# JugendNetzteil.net
KiCad netlist of a schematic drawn in EAGLE
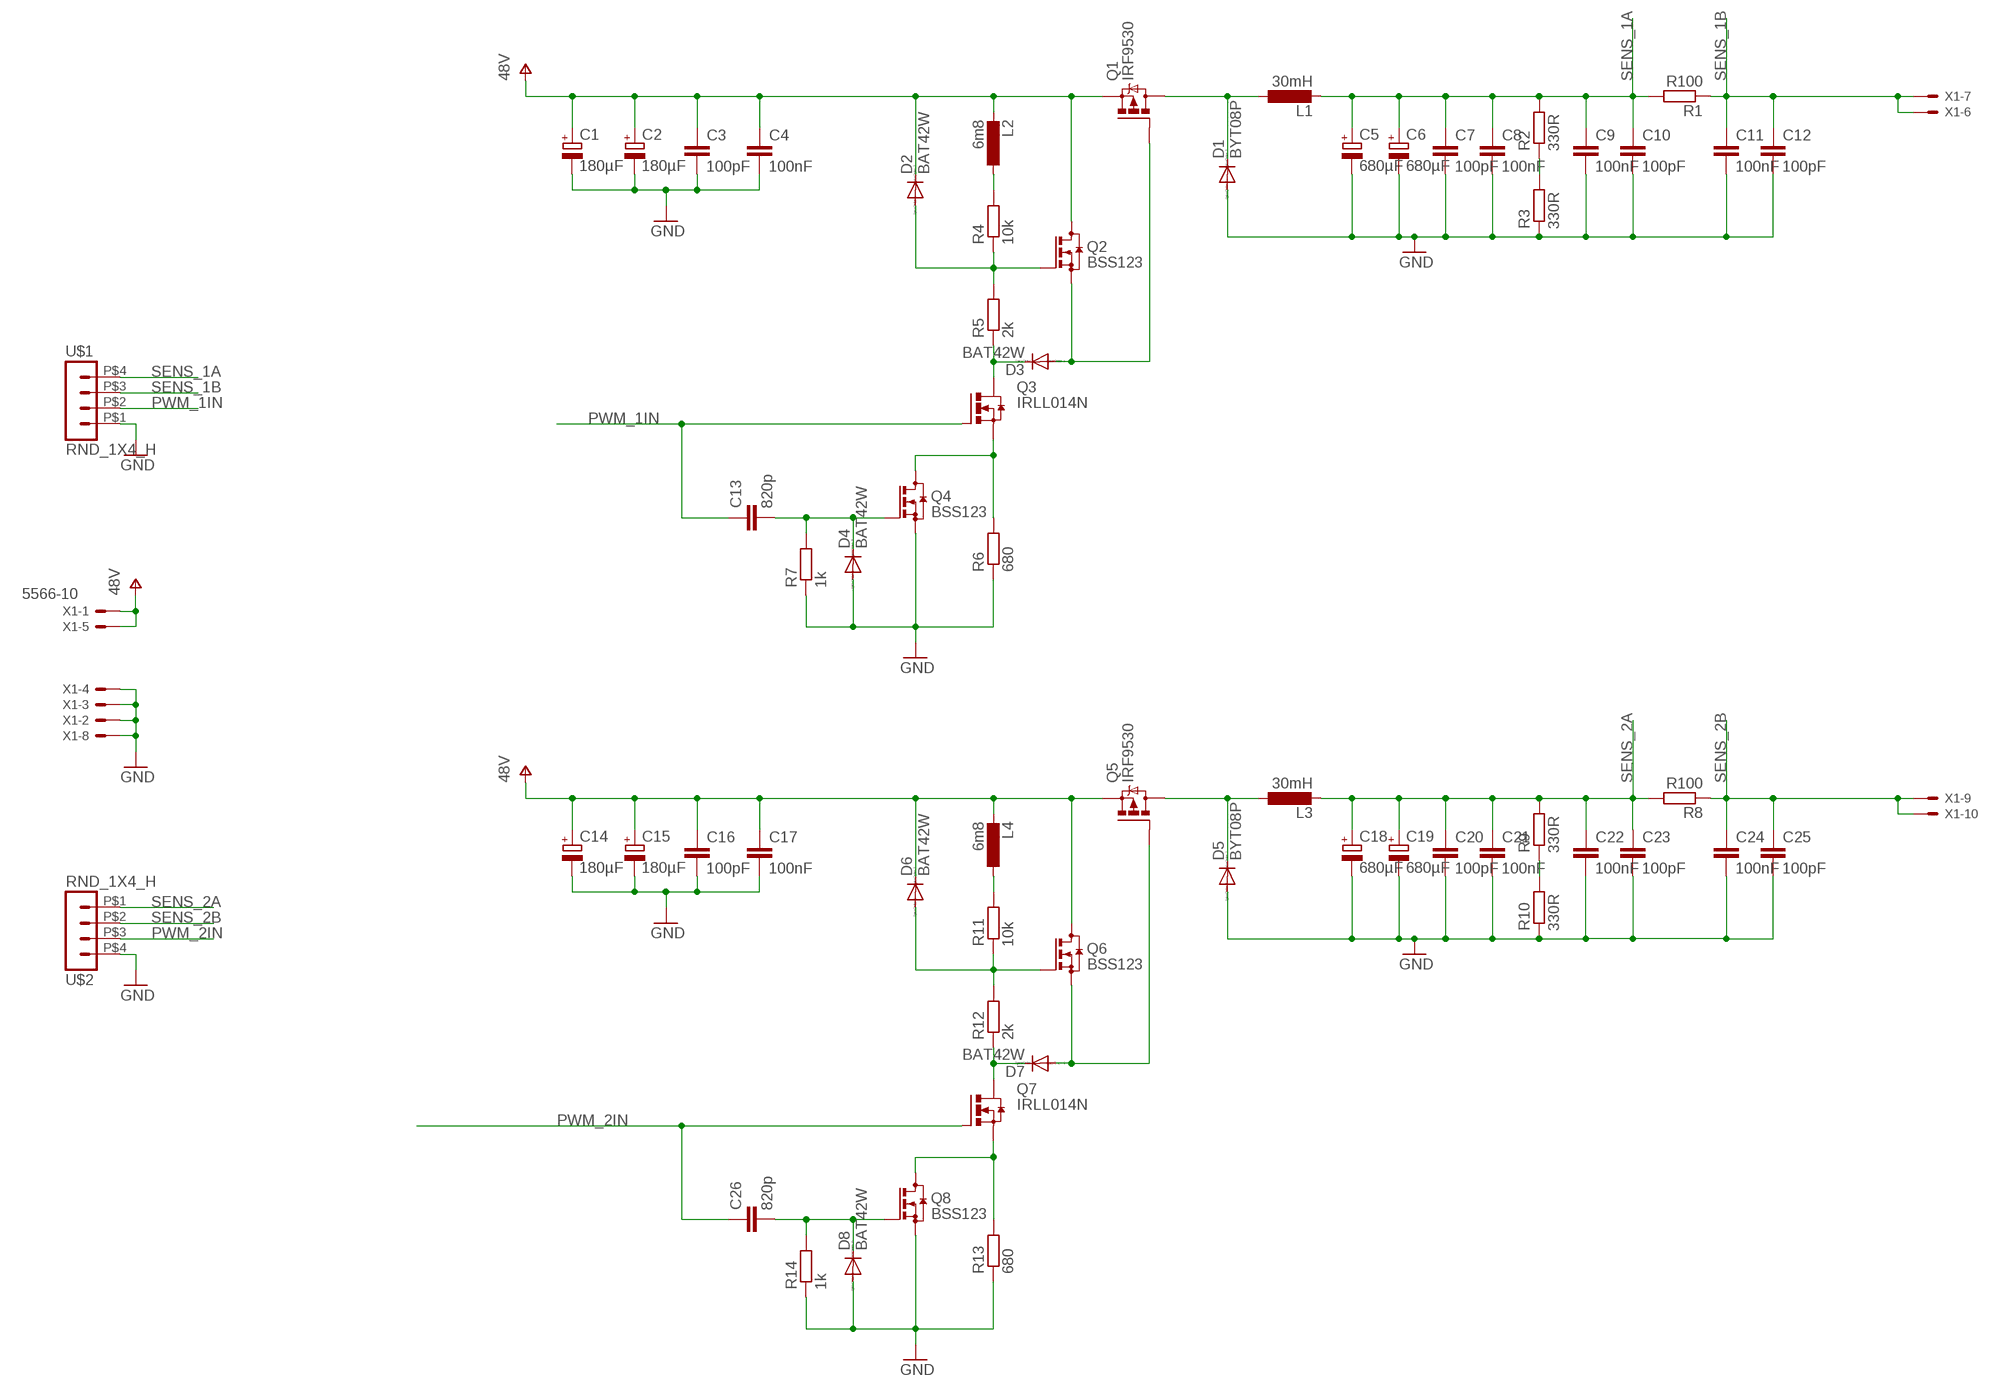
[diagram p0: schematic, sheet 1]

(export (version "E")
  (design (tool "Eeschema 10.0.6"))
  (components
    (comp (ref "C1")
      (value "180µF")
      (footprint "eagle-import:E3,5-8")
      (libsource (lib "eagle-import") (part "CPOL-EUE3.5-8"))
    )
    (comp (ref "C2")
      (value "180µF")
      (footprint "eagle-import:E3,5-8")
      (libsource (lib "eagle-import") (part "CPOL-EUE3.5-8"))
    )
    (comp (ref "C3")
      (value "100pF")
      (footprint "eagle-import:C0805")
      (libsource (lib "eagle-import") (part "C-EUC0805"))
    )
    (comp (ref "C4")
      (value "100nF")
      (footprint "eagle-import:C0805")
      (libsource (lib "eagle-import") (part "C-EUC0805"))
    )
    (comp (ref "C5")
      (value "680µF")
      (footprint "eagle-import:TT5D11")
      (libsource (lib "eagle-import") (part "CPOL-EUTT5D11"))
    )
    (comp (ref "C6")
      (value "680µF")
      (footprint "eagle-import:TT5D11")
      (libsource (lib "eagle-import") (part "CPOL-EUTT5D11"))
    )
    (comp (ref "C7")
      (value "100pF")
      (footprint "eagle-import:C0805")
      (libsource (lib "eagle-import") (part "C-EUC0805"))
    )
    (comp (ref "C8")
      (value "100nF")
      (footprint "eagle-import:C0805")
      (libsource (lib "eagle-import") (part "C-EUC0805"))
    )
    (comp (ref "C9")
      (value "100nF")
      (footprint "eagle-import:C0805")
      (libsource (lib "eagle-import") (part "C-EUC0805"))
    )
    (comp (ref "C10")
      (value "100pF")
      (footprint "eagle-import:C0805")
      (libsource (lib "eagle-import") (part "C-EUC0805"))
    )
    (comp (ref "C11")
      (value "100nF")
      (footprint "eagle-import:C0805")
      (libsource (lib "eagle-import") (part "C-EUC0805"))
    )
    (comp (ref "C12")
      (value "100pF")
      (footprint "eagle-import:C0805")
      (libsource (lib "eagle-import") (part "C-EUC0805"))
    )
    (comp (ref "C13")
      (value "820p")
      (footprint "eagle-import:C0805")
      (libsource (lib "eagle-import") (part "resistor_348_C-EUC0805"))
    )
    (comp (ref "C14")
      (value "180µF")
      (footprint "eagle-import:E3,5-8")
      (libsource (lib "eagle-import") (part "CPOL-EUE3.5-8"))
    )
    (comp (ref "C15")
      (value "180µF")
      (footprint "eagle-import:E3,5-8")
      (libsource (lib "eagle-import") (part "CPOL-EUE3.5-8"))
    )
    (comp (ref "C16")
      (value "100pF")
      (footprint "eagle-import:C0805")
      (libsource (lib "eagle-import") (part "C-EUC0805"))
    )
    (comp (ref "C17")
      (value "100nF")
      (footprint "eagle-import:C0805")
      (libsource (lib "eagle-import") (part "C-EUC0805"))
    )
    (comp (ref "C18")
      (value "680µF")
      (footprint "eagle-import:TT5D11")
      (libsource (lib "eagle-import") (part "CPOL-EUTT5D11"))
    )
    (comp (ref "C19")
      (value "680µF")
      (footprint "eagle-import:TT5D11")
      (libsource (lib "eagle-import") (part "CPOL-EUTT5D11"))
    )
    (comp (ref "C20")
      (value "100pF")
      (footprint "eagle-import:C0805")
      (libsource (lib "eagle-import") (part "C-EUC0805"))
    )
    (comp (ref "C21")
      (value "100nF")
      (footprint "eagle-import:C0805")
      (libsource (lib "eagle-import") (part "C-EUC0805"))
    )
    (comp (ref "C22")
      (value "100nF")
      (footprint "eagle-import:C0805")
      (libsource (lib "eagle-import") (part "C-EUC0805"))
    )
    (comp (ref "C23")
      (value "100pF")
      (footprint "eagle-import:C0805")
      (libsource (lib "eagle-import") (part "C-EUC0805"))
    )
    (comp (ref "C24")
      (value "100nF")
      (footprint "eagle-import:C0805")
      (libsource (lib "eagle-import") (part "C-EUC0805"))
    )
    (comp (ref "C25")
      (value "100pF")
      (footprint "eagle-import:C0805")
      (libsource (lib "eagle-import") (part "C-EUC0805"))
    )
    (comp (ref "C26")
      (value "820p")
      (footprint "eagle-import:C0805")
      (libsource (lib "eagle-import") (part "resistor_348_C-EUC0805"))
    )
    (comp (ref "D1")
      (value "BYT08P")
      (footprint "eagle-import:TO220ACS")
      (libsource (lib "eagle-import") (part "BYT08P"))
    )
    (comp (ref "D2")
      (value "BAT42W")
      (footprint "eagle-import:SOD123")
      (libsource (lib "eagle-import") (part "DIODE-SOD123"))
    )
    (comp (ref "D3")
      (value "BAT42W")
      (footprint "eagle-import:SOD123")
      (libsource (lib "eagle-import") (part "DIODE-SOD123"))
    )
    (comp (ref "D4")
      (value "BAT42W")
      (footprint "eagle-import:SOD123")
      (libsource (lib "eagle-import") (part "DIODE-SOD123"))
    )
    (comp (ref "D5")
      (value "BYT08P")
      (footprint "eagle-import:TO220ACS")
      (libsource (lib "eagle-import") (part "BYT08P"))
    )
    (comp (ref "D6")
      (value "BAT42W")
      (footprint "eagle-import:SOD123")
      (libsource (lib "eagle-import") (part "DIODE-SOD123"))
    )
    (comp (ref "D7")
      (value "BAT42W")
      (footprint "eagle-import:SOD123")
      (libsource (lib "eagle-import") (part "DIODE-SOD123"))
    )
    (comp (ref "D8")
      (value "BAT42W")
      (footprint "eagle-import:SOD123")
      (libsource (lib "eagle-import") (part "DIODE-SOD123"))
    )
    (comp (ref "L1")
      (value "30mH")
      (footprint "eagle-import:TJ8-U1")
      (libsource (lib "eagle-import") (part "L-EUTJ8-U1"))
    )
    (comp (ref "L2")
      (value "6m8")
      (footprint "eagle-import:2200-15.24")
      (libsource (lib "eagle-import") (part "L-EU2200-15.24"))
    )
    (comp (ref "L3")
      (value "30mH")
      (footprint "eagle-import:TJ8-U1")
      (libsource (lib "eagle-import") (part "L-EUTJ8-U1"))
    )
    (comp (ref "L4")
      (value "6m8")
      (footprint "eagle-import:2200-15.24")
      (libsource (lib "eagle-import") (part "L-EU2200-15.24"))
    )
    (comp (ref "Q1")
      (value "IRF9530")
      (footprint "eagle-import:TO220BV")
      (libsource (lib "eagle-import") (part "IRF9530"))
    )
    (comp (ref "Q2")
      (value "BSS123")
      (footprint "eagle-import:SOT23")
      (libsource (lib "eagle-import") (part "BSS123"))
    )
    (comp (ref "Q3")
      (value "IRLL014N")
      (footprint "eagle-import:SOT223")
      (libsource (lib "eagle-import") (part "N-HEXFET-2D_?-SOT232"))
    )
    (comp (ref "Q4")
      (value "BSS123")
      (footprint "eagle-import:SOT23")
      (libsource (lib "eagle-import") (part "BSS123"))
    )
    (comp (ref "Q5")
      (value "IRF9530")
      (footprint "eagle-import:TO220BV")
      (libsource (lib "eagle-import") (part "IRF9530"))
    )
    (comp (ref "Q6")
      (value "BSS123")
      (footprint "eagle-import:SOT23")
      (libsource (lib "eagle-import") (part "BSS123"))
    )
    (comp (ref "Q7")
      (value "IRLL014N")
      (footprint "eagle-import:SOT223")
      (libsource (lib "eagle-import") (part "N-HEXFET-2D_?-SOT232"))
    )
    (comp (ref "Q8")
      (value "BSS123")
      (footprint "eagle-import:SOT23")
      (libsource (lib "eagle-import") (part "BSS123"))
    )
    (comp (ref "R1")
      (value "R100")
      (footprint "eagle-import:0617V")
      (libsource (lib "eagle-import") (part "R-EU_0617/5V"))
    )
    (comp (ref "R2")
      (value "330R")
      (footprint "eagle-import:0414V")
      (libsource (lib "eagle-import") (part "R-EU_0414/5V"))
    )
    (comp (ref "R3")
      (value "330R")
      (footprint "eagle-import:0414V")
      (libsource (lib "eagle-import") (part "R-EU_0414/5V"))
    )
    (comp (ref "R4")
      (value "10k")
      (footprint "eagle-import:R0805")
      (libsource (lib "eagle-import") (part "resistor_348_R-EU_R0805"))
    )
    (comp (ref "R5")
      (value "2k")
      (footprint "eagle-import:R0805")
      (libsource (lib "eagle-import") (part "resistor_348_R-EU_R0805"))
    )
    (comp (ref "R6")
      (value "680")
      (footprint "eagle-import:R0805")
      (libsource (lib "eagle-import") (part "resistor_348_R-EU_R0805"))
    )
    (comp (ref "R7")
      (value "1k")
      (footprint "eagle-import:R0805")
      (libsource (lib "eagle-import") (part "resistor_348_R-EU_R0805"))
    )
    (comp (ref "R8")
      (value "R100")
      (footprint "eagle-import:0617V")
      (libsource (lib "eagle-import") (part "R-EU_0617/5V"))
    )
    (comp (ref "R9")
      (value "330R")
      (footprint "eagle-import:0414V")
      (libsource (lib "eagle-import") (part "R-EU_0414/5V"))
    )
    (comp (ref "R10")
      (value "330R")
      (footprint "eagle-import:0414V")
      (libsource (lib "eagle-import") (part "R-EU_0414/5V"))
    )
    (comp (ref "R11")
      (value "10k")
      (footprint "eagle-import:R0805")
      (libsource (lib "eagle-import") (part "resistor_348_R-EU_R0805"))
    )
    (comp (ref "R12")
      (value "2k")
      (footprint "eagle-import:R0805")
      (libsource (lib "eagle-import") (part "resistor_348_R-EU_R0805"))
    )
    (comp (ref "R13")
      (value "680")
      (footprint "eagle-import:R0805")
      (libsource (lib "eagle-import") (part "resistor_348_R-EU_R0805"))
    )
    (comp (ref "R14")
      (value "1k")
      (footprint "eagle-import:R0805")
      (libsource (lib "eagle-import") (part "resistor_348_R-EU_R0805"))
    )
    (comp (ref "U$1")
      (value "RND_1X4_H")
      (footprint "eagle-import:RND_1X4_H")
      (libsource (lib "eagle-import") (part "RND_1X4_H"))
    )
    (comp (ref "U$2")
      (value "RND_1X4_H")
      (footprint "eagle-import:RND_1X4_H")
      (libsource (lib "eagle-import") (part "RND_1X4_H"))
    )
    (comp (ref "X1")
      (value "5566-10")
      (footprint "eagle-import:5566-10")
      (libsource (lib "eagle-import") (part "5566-10"))
    )
  )
  (nets
    (net (code "1") (name "/PWM_1IN") (class "Default")
      (node (ref "C13") (pin "1") (pinfunction "1_1") (pintype "passive"))
      (node (ref "Q3") (pin "1") (pinfunction "G_1") (pintype "passive"))
      (node (ref "U$1") (pin "P$2") (pinfunction "2_P$2") (pintype "passive"))
    )
    (net (code "2") (name "/PWM_2IN") (class "Default")
      (node (ref "C26") (pin "1") (pinfunction "1_1") (pintype "passive"))
      (node (ref "Q7") (pin "1") (pinfunction "G_1") (pintype "passive"))
      (node (ref "U$2") (pin "P$3") (pinfunction "3_P$3") (pintype "passive"))
    )
    (net (code "3") (name "/SENS_1A") (class "Default")
      (node (ref "C10") (pin "1") (pinfunction "1_1") (pintype "passive"))
      (node (ref "C5") (pin "+") (pinfunction "+_+") (pintype "passive"))
      (node (ref "C6") (pin "+") (pinfunction "+_+") (pintype "passive"))
      (node (ref "C7") (pin "1") (pinfunction "1_1") (pintype "passive"))
      (node (ref "C8") (pin "1") (pinfunction "1_1") (pintype "passive"))
      (node (ref "C9") (pin "1") (pinfunction "1_1") (pintype "passive"))
      (node (ref "L1") (pin "2") (pinfunction "2_2") (pintype "passive"))
      (node (ref "R1") (pin "2") (pinfunction "2_2") (pintype "passive"))
      (node (ref "R2") (pin "2") (pinfunction "2_2") (pintype "passive"))
      (node (ref "U$1") (pin "P$4") (pinfunction "4_P$4") (pintype "passive"))
    )
    (net (code "4") (name "/SENS_1B") (class "Default")
      (node (ref "C11") (pin "1") (pinfunction "1_1") (pintype "passive"))
      (node (ref "C12") (pin "1") (pinfunction "1_1") (pintype "passive"))
      (node (ref "R1") (pin "1") (pinfunction "1_1") (pintype "passive"))
      (node (ref "U$1") (pin "P$3") (pinfunction "3_P$3") (pintype "passive"))
      (node (ref "X1") (pin "6") (pinfunction "S_6") (pintype "passive"))
      (node (ref "X1") (pin "7") (pinfunction "S_7") (pintype "passive"))
    )
    (net (code "5") (name "/SENS_2A") (class "Default")
      (node (ref "C18") (pin "+") (pinfunction "+_+") (pintype "passive"))
      (node (ref "C19") (pin "+") (pinfunction "+_+") (pintype "passive"))
      (node (ref "C20") (pin "1") (pinfunction "1_1") (pintype "passive"))
      (node (ref "C21") (pin "1") (pinfunction "1_1") (pintype "passive"))
      (node (ref "C22") (pin "1") (pinfunction "1_1") (pintype "passive"))
      (node (ref "C23") (pin "1") (pinfunction "1_1") (pintype "passive"))
      (node (ref "L3") (pin "2") (pinfunction "2_2") (pintype "passive"))
      (node (ref "R8") (pin "2") (pinfunction "2_2") (pintype "passive"))
      (node (ref "R9") (pin "2") (pinfunction "2_2") (pintype "passive"))
      (node (ref "U$2") (pin "P$1") (pinfunction "1_P$1") (pintype "passive"))
    )
    (net (code "6") (name "/SENS_2B") (class "Default")
      (node (ref "C24") (pin "1") (pinfunction "1_1") (pintype "passive"))
      (node (ref "C25") (pin "1") (pinfunction "1_1") (pintype "passive"))
      (node (ref "R8") (pin "1") (pinfunction "1_1") (pintype "passive"))
      (node (ref "U$2") (pin "P$2") (pinfunction "2_P$2") (pintype "passive"))
      (node (ref "X1") (pin "10") (pinfunction "S_10") (pintype "passive"))
      (node (ref "X1") (pin "9") (pinfunction "S_9") (pintype "passive"))
    )
    (net (code "7") (name "48V") (class "Default")
      (node (ref "C1") (pin "+") (pinfunction "+_+") (pintype "passive"))
      (node (ref "C14") (pin "+") (pinfunction "+_+") (pintype "passive"))
      (node (ref "C15") (pin "+") (pinfunction "+_+") (pintype "passive"))
      (node (ref "C16") (pin "1") (pinfunction "1_1") (pintype "passive"))
      (node (ref "C17") (pin "1") (pinfunction "1_1") (pintype "passive"))
      (node (ref "C2") (pin "+") (pinfunction "+_+") (pintype "passive"))
      (node (ref "C3") (pin "1") (pinfunction "1_1") (pintype "passive"))
      (node (ref "C4") (pin "1") (pinfunction "1_1") (pintype "passive"))
      (node (ref "D2") (pin "C") (pinfunction "C_C") (pintype "passive"))
      (node (ref "D6") (pin "C") (pinfunction "C_C") (pintype "passive"))
      (node (ref "L2") (pin "2") (pinfunction "2_2") (pintype "passive"))
      (node (ref "L4") (pin "2") (pinfunction "2_2") (pintype "passive"))
      (node (ref "Q1") (pin "S") (pinfunction "S_S") (pintype "passive"))
      (node (ref "Q2") (pin "3") (pinfunction "D_3") (pintype "passive"))
      (node (ref "Q5") (pin "S") (pinfunction "S_S") (pintype "passive"))
      (node (ref "Q6") (pin "3") (pinfunction "D_3") (pintype "passive"))
      (node (ref "X1") (pin "1") (pinfunction "S_1") (pintype "passive"))
      (node (ref "X1") (pin "5") (pinfunction "S_5") (pintype "passive"))
    )
    (net (code "8") (name "GND") (class "Default")
      (node (ref "C1") (pin "-") (pinfunction "-_-") (pintype "passive"))
      (node (ref "C10") (pin "2") (pinfunction "2_2") (pintype "passive"))
      (node (ref "C11") (pin "2") (pinfunction "2_2") (pintype "passive"))
      (node (ref "C12") (pin "2") (pinfunction "2_2") (pintype "passive"))
      (node (ref "C14") (pin "-") (pinfunction "-_-") (pintype "passive"))
      (node (ref "C15") (pin "-") (pinfunction "-_-") (pintype "passive"))
      (node (ref "C16") (pin "2") (pinfunction "2_2") (pintype "passive"))
      (node (ref "C17") (pin "2") (pinfunction "2_2") (pintype "passive"))
      (node (ref "C18") (pin "-") (pinfunction "-_-") (pintype "passive"))
      (node (ref "C19") (pin "-") (pinfunction "-_-") (pintype "passive"))
      (node (ref "C2") (pin "-") (pinfunction "-_-") (pintype "passive"))
      (node (ref "C20") (pin "2") (pinfunction "2_2") (pintype "passive"))
      (node (ref "C21") (pin "2") (pinfunction "2_2") (pintype "passive"))
      (node (ref "C22") (pin "2") (pinfunction "2_2") (pintype "passive"))
      (node (ref "C23") (pin "2") (pinfunction "2_2") (pintype "passive"))
      (node (ref "C24") (pin "2") (pinfunction "2_2") (pintype "passive"))
      (node (ref "C25") (pin "2") (pinfunction "2_2") (pintype "passive"))
      (node (ref "C3") (pin "2") (pinfunction "2_2") (pintype "passive"))
      (node (ref "C4") (pin "2") (pinfunction "2_2") (pintype "passive"))
      (node (ref "C5") (pin "-") (pinfunction "-_-") (pintype "passive"))
      (node (ref "C6") (pin "-") (pinfunction "-_-") (pintype "passive"))
      (node (ref "C7") (pin "2") (pinfunction "2_2") (pintype "passive"))
      (node (ref "C8") (pin "2") (pinfunction "2_2") (pintype "passive"))
      (node (ref "C9") (pin "2") (pinfunction "2_2") (pintype "passive"))
      (node (ref "D1") (pin "A") (pinfunction "A_A") (pintype "passive"))
      (node (ref "D4") (pin "A") (pinfunction "A_A") (pintype "passive"))
      (node (ref "D5") (pin "A") (pinfunction "A_A") (pintype "passive"))
      (node (ref "D8") (pin "A") (pinfunction "A_A") (pintype "passive"))
      (node (ref "Q4") (pin "2") (pinfunction "S_2") (pintype "passive"))
      (node (ref "Q8") (pin "2") (pinfunction "S_2") (pintype "passive"))
      (node (ref "R10") (pin "1") (pinfunction "1_1") (pintype "passive"))
      (node (ref "R13") (pin "1") (pinfunction "1_1") (pintype "passive"))
      (node (ref "R14") (pin "1") (pinfunction "1_1") (pintype "passive"))
      (node (ref "R3") (pin "1") (pinfunction "1_1") (pintype "passive"))
      (node (ref "R6") (pin "1") (pinfunction "1_1") (pintype "passive"))
      (node (ref "R7") (pin "1") (pinfunction "1_1") (pintype "passive"))
      (node (ref "U$1") (pin "P$1") (pinfunction "1_P$1") (pintype "passive"))
      (node (ref "U$2") (pin "P$4") (pinfunction "4_P$4") (pintype "passive"))
      (node (ref "X1") (pin "2") (pinfunction "S_2") (pintype "passive"))
      (node (ref "X1") (pin "3") (pinfunction "S_3") (pintype "passive"))
      (node (ref "X1") (pin "4") (pinfunction "S_4") (pintype "passive"))
      (node (ref "X1") (pin "8") (pinfunction "S_8") (pintype "passive"))
    )
    (net (code "9") (name "Net-(D1-PadC)") (class "Default")
      (node (ref "D1") (pin "C") (pinfunction "C_C") (pintype "passive"))
      (node (ref "L1") (pin "1") (pinfunction "1_1") (pintype "passive"))
      (node (ref "Q1") (pin "D") (pinfunction "D_D") (pintype "passive"))
    )
    (net (code "10") (name "Net-(D3-PadC)") (class "Default")
      (node (ref "D3") (pin "C") (pinfunction "C_C") (pintype "passive"))
      (node (ref "Q3") (pin "2") (pinfunction "D_2") (pintype "passive"))
      (node (ref "Q3") (pin "4") (pinfunction "D_4") (pintype "passive"))
      (node (ref "R5") (pin "1") (pinfunction "1_1") (pintype "passive"))
    )
    (net (code "11") (name "Net-(D5-PadC)") (class "Default")
      (node (ref "D5") (pin "C") (pinfunction "C_C") (pintype "passive"))
      (node (ref "L3") (pin "1") (pinfunction "1_1") (pintype "passive"))
      (node (ref "Q5") (pin "D") (pinfunction "D_D") (pintype "passive"))
    )
    (net (code "12") (name "Net-(D7-PadC)") (class "Default")
      (node (ref "D7") (pin "C") (pinfunction "C_C") (pintype "passive"))
      (node (ref "Q7") (pin "2") (pinfunction "D_2") (pintype "passive"))
      (node (ref "Q7") (pin "4") (pinfunction "D_4") (pintype "passive"))
      (node (ref "R12") (pin "1") (pinfunction "1_1") (pintype "passive"))
    )
    (net (code "13") (name "Net-(L2-Pad1)") (class "Default")
      (node (ref "L2") (pin "1") (pinfunction "1_1") (pintype "passive"))
      (node (ref "R4") (pin "2") (pinfunction "2_2") (pintype "passive"))
    )
    (net (code "14") (name "Net-(L4-Pad1)") (class "Default")
      (node (ref "L4") (pin "1") (pinfunction "1_1") (pintype "passive"))
      (node (ref "R11") (pin "2") (pinfunction "2_2") (pintype "passive"))
    )
    (net (code "15") (name "Net-(Q2-G)") (class "Default")
      (node (ref "D2") (pin "A") (pinfunction "A_A") (pintype "passive"))
      (node (ref "Q2") (pin "1") (pinfunction "G_1") (pintype "passive"))
      (node (ref "R4") (pin "1") (pinfunction "1_1") (pintype "passive"))
      (node (ref "R5") (pin "2") (pinfunction "2_2") (pintype "passive"))
    )
    (net (code "16") (name "Net-(Q2-S)") (class "Default")
      (node (ref "D3") (pin "A") (pinfunction "A_A") (pintype "passive"))
      (node (ref "Q1") (pin "G") (pinfunction "G_G") (pintype "passive"))
      (node (ref "Q2") (pin "2") (pinfunction "S_2") (pintype "passive"))
    )
    (net (code "17") (name "Net-(Q3-S)") (class "Default")
      (node (ref "Q3") (pin "3") (pinfunction "S_3") (pintype "passive"))
      (node (ref "Q4") (pin "3") (pinfunction "D_3") (pintype "passive"))
      (node (ref "R6") (pin "2") (pinfunction "2_2") (pintype "passive"))
    )
    (net (code "18") (name "Net-(Q4-G)") (class "Default")
      (node (ref "C13") (pin "2") (pinfunction "2_2") (pintype "passive"))
      (node (ref "D4") (pin "C") (pinfunction "C_C") (pintype "passive"))
      (node (ref "Q4") (pin "1") (pinfunction "G_1") (pintype "passive"))
      (node (ref "R7") (pin "2") (pinfunction "2_2") (pintype "passive"))
    )
    (net (code "19") (name "Net-(Q6-G)") (class "Default")
      (node (ref "D6") (pin "A") (pinfunction "A_A") (pintype "passive"))
      (node (ref "Q6") (pin "1") (pinfunction "G_1") (pintype "passive"))
      (node (ref "R11") (pin "1") (pinfunction "1_1") (pintype "passive"))
      (node (ref "R12") (pin "2") (pinfunction "2_2") (pintype "passive"))
    )
    (net (code "20") (name "Net-(Q6-S)") (class "Default")
      (node (ref "D7") (pin "A") (pinfunction "A_A") (pintype "passive"))
      (node (ref "Q5") (pin "G") (pinfunction "G_G") (pintype "passive"))
      (node (ref "Q6") (pin "2") (pinfunction "S_2") (pintype "passive"))
    )
    (net (code "21") (name "Net-(Q7-S)") (class "Default")
      (node (ref "Q7") (pin "3") (pinfunction "S_3") (pintype "passive"))
      (node (ref "Q8") (pin "3") (pinfunction "D_3") (pintype "passive"))
      (node (ref "R13") (pin "2") (pinfunction "2_2") (pintype "passive"))
    )
    (net (code "22") (name "Net-(Q8-G)") (class "Default")
      (node (ref "C26") (pin "2") (pinfunction "2_2") (pintype "passive"))
      (node (ref "D8") (pin "C") (pinfunction "C_C") (pintype "passive"))
      (node (ref "Q8") (pin "1") (pinfunction "G_1") (pintype "passive"))
      (node (ref "R14") (pin "2") (pinfunction "2_2") (pintype "passive"))
    )
    (net (code "23") (name "Net-(R2-Pad1)") (class "Default")
      (node (ref "R2") (pin "1") (pinfunction "1_1") (pintype "passive"))
      (node (ref "R3") (pin "2") (pinfunction "2_2") (pintype "passive"))
    )
    (net (code "24") (name "Net-(R10-Pad2)") (class "Default")
      (node (ref "R10") (pin "2") (pinfunction "2_2") (pintype "passive"))
      (node (ref "R9") (pin "1") (pinfunction "1_1") (pintype "passive"))
    )
  )
)
